# BM1397_TESTBED.net
KiCad netlist of a schematic drawn in Altium Designer
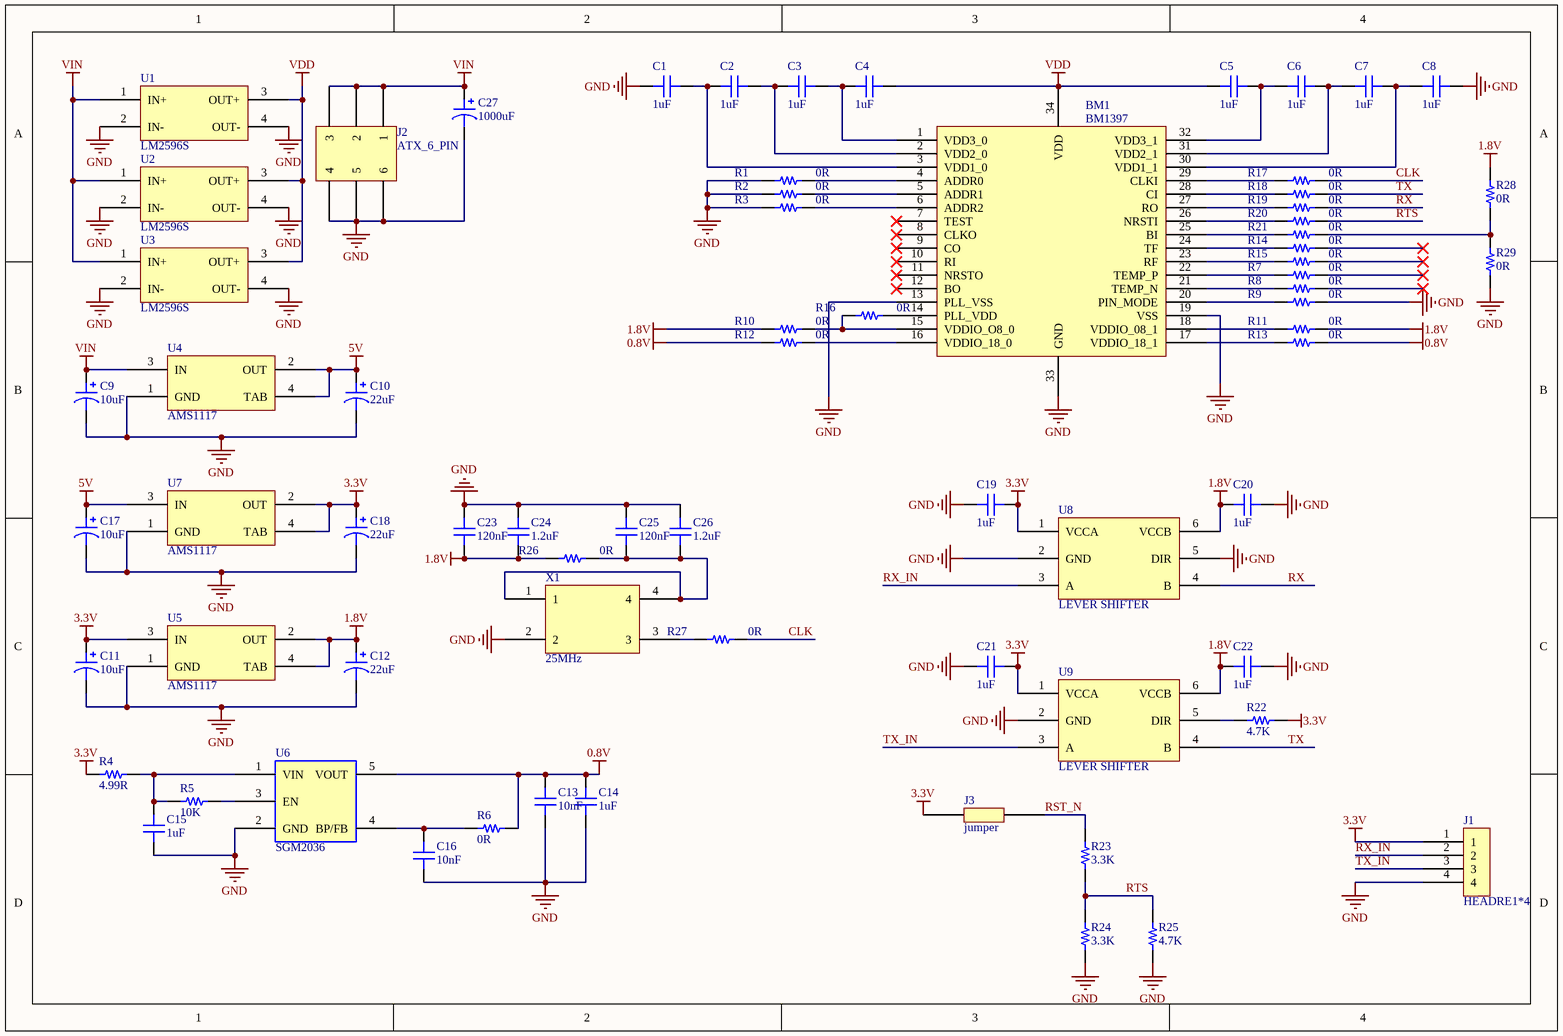
[diagram p0: BM1397_TESTBED.SchDoc]

(export (version "E")
  (design (tool "Eeschema 10.0.6"))
  (components
    (comp (ref "BM1")
      (value "BM1397")
      (footprint "Connector")
      (libsource (lib "BM1397_TESTBED") (part "BM1397_0"))
    )
    (comp (ref "C1") (value "1uF") (footprint "CAP_SMD_0805") (libsource (lib "BM1397_TESTBED") (part "CAP")))
    (comp (ref "C2") (value "1uF") (footprint "CAP_SMD_0805") (libsource (lib "BM1397_TESTBED") (part "CAP")))
    (comp (ref "C3") (value "1uF") (footprint "CAP_SMD_0805") (libsource (lib "BM1397_TESTBED") (part "CAP")))
    (comp (ref "C4") (value "1uF") (footprint "CAP_SMD_0805") (libsource (lib "BM1397_TESTBED") (part "CAP")))
    (comp (ref "C5") (value "1uF") (footprint "CAP_SMD_0805") (libsource (lib "BM1397_TESTBED") (part "CAP")))
    (comp (ref "C6") (value "1uF") (footprint "CAP_SMD_0805") (libsource (lib "BM1397_TESTBED") (part "CAP")))
    (comp (ref "C7") (value "1uF") (footprint "CAP_SMD_0805") (libsource (lib "BM1397_TESTBED") (part "CAP")))
    (comp (ref "C8") (value "1uF") (footprint "CAP_SMD_0805") (libsource (lib "BM1397_TESTBED") (part "CAP")))
    (comp (ref "C9")
      (value "10uF")
      (footprint "CAP-TAN-CASE-B")
      (libsource (lib "BM1397_TESTBED") (part "POLARIZED CAP"))
    )
    (comp (ref "C10")
      (value "22uF")
      (footprint "CAP-TAN-CASE-B")
      (libsource (lib "BM1397_TESTBED") (part "POLARIZED CAP"))
    )
    (comp (ref "C11")
      (value "10uF")
      (footprint "CAP-TAN-CASE-B")
      (libsource (lib "BM1397_TESTBED") (part "POLARIZED CAP"))
    )
    (comp (ref "C12")
      (value "22uF")
      (footprint "CAP-TAN-CASE-B")
      (libsource (lib "BM1397_TESTBED") (part "POLARIZED CAP"))
    )
    (comp (ref "C13")
      (value "10nF")
      (footprint "CAP_SMD_0805")
      (libsource (lib "BM1397_TESTBED") (part "CAP"))
    )
    (comp (ref "C14")
      (value "1uF")
      (footprint "CAP_SMD_0805")
      (libsource (lib "BM1397_TESTBED") (part "CAP"))
    )
    (comp (ref "C15")
      (value "1uF")
      (footprint "CAP_SMD_0805")
      (libsource (lib "BM1397_TESTBED") (part "CAP"))
    )
    (comp (ref "C16")
      (value "10nF")
      (footprint "CAP_SMD_0805")
      (libsource (lib "BM1397_TESTBED") (part "CAP"))
    )
    (comp (ref "C17")
      (value "10uF")
      (footprint "CAP-TAN-CASE-B")
      (libsource (lib "BM1397_TESTBED") (part "POLARIZED CAP"))
    )
    (comp (ref "C18")
      (value "22uF")
      (footprint "CAP-TAN-CASE-B")
      (libsource (lib "BM1397_TESTBED") (part "POLARIZED CAP"))
    )
    (comp (ref "C19")
      (value "1uF")
      (footprint "CAP_SMD_0805")
      (libsource (lib "BM1397_TESTBED") (part "CAP"))
    )
    (comp (ref "C20")
      (value "1uF")
      (footprint "CAP_SMD_0805")
      (libsource (lib "BM1397_TESTBED") (part "CAP"))
    )
    (comp (ref "C21")
      (value "1uF")
      (footprint "CAP_SMD_0805")
      (libsource (lib "BM1397_TESTBED") (part "CAP"))
    )
    (comp (ref "C22")
      (value "1uF")
      (footprint "CAP_SMD_0805")
      (libsource (lib "BM1397_TESTBED") (part "CAP"))
    )
    (comp (ref "C23")
      (value "120nF")
      (footprint "CAP_SMD_1206")
      (libsource (lib "BM1397_TESTBED") (part "CAP"))
    )
    (comp (ref "C24")
      (value "1.2uF")
      (footprint "CAP_SMD_1206")
      (libsource (lib "BM1397_TESTBED") (part "CAP"))
    )
    (comp (ref "C25")
      (value "120nF")
      (footprint "CAP_SMD_1206")
      (libsource (lib "BM1397_TESTBED") (part "CAP"))
    )
    (comp (ref "C26")
      (value "1.2uF")
      (footprint "CAP_SMD_1206")
      (libsource (lib "BM1397_TESTBED") (part "CAP"))
    )
    (comp (ref "C27")
      (value "1000uF")
      (footprint "CAP_POL")
      (libsource (lib "BM1397_TESTBED") (part "POLARIZED CAP"))
    )
    (comp (ref "J1")
      (value "HEADRE1*4")
      (footprint "HEADER-1x4")
      (libsource (lib "BM1397_TESTBED") (part "HEADER-1x4"))
    )
    (comp (ref "J2")
      (value "ATX_6_PIN")
      (footprint "ATX 6")
      (description "ATX PWR CONN 6 PIN")
      (libsource (lib "BM1397_TESTBED") (part "ATX_6_PIN"))
    )
    (comp (ref "J3")
      (value "jumper")
      (footprint "jumper_2pin")
      (libsource (lib "BM1397_TESTBED") (part "Jumper_2"))
    )
    (comp (ref "R1") (value "0R") (footprint "RES-SMD-1206") (libsource (lib "BM1397_TESTBED") (part "RES")))
    (comp (ref "R2") (value "0R") (footprint "RES-SMD-1206") (libsource (lib "BM1397_TESTBED") (part "RES")))
    (comp (ref "R3") (value "0R") (footprint "RES-SMD-1206") (libsource (lib "BM1397_TESTBED") (part "RES")))
    (comp (ref "R4")
      (value "4.99R")
      (footprint "RES-SMD-1206")
      (libsource (lib "BM1397_TESTBED") (part "RES"))
    )
    (comp (ref "R5") (value "10K") (footprint "RES-SMD-1206") (libsource (lib "BM1397_TESTBED") (part "RES")))
    (comp (ref "R6") (value "0R") (footprint "RES-SMD-1206") (libsource (lib "BM1397_TESTBED") (part "RES")))
    (comp (ref "R7") (value "0R") (footprint "RES-SMD-1206") (libsource (lib "BM1397_TESTBED") (part "RES")))
    (comp (ref "R8") (value "0R") (footprint "RES-SMD-1206") (libsource (lib "BM1397_TESTBED") (part "RES")))
    (comp (ref "R9") (value "0R") (footprint "RES-SMD-1206") (libsource (lib "BM1397_TESTBED") (part "RES")))
    (comp (ref "R10") (value "0R") (footprint "RES-SMD-1206") (libsource (lib "BM1397_TESTBED") (part "RES")))
    (comp (ref "R11") (value "0R") (footprint "RES-SMD-1206") (libsource (lib "BM1397_TESTBED") (part "RES")))
    (comp (ref "R12") (value "0R") (footprint "RES-SMD-1206") (libsource (lib "BM1397_TESTBED") (part "RES")))
    (comp (ref "R13") (value "0R") (footprint "RES-SMD-1206") (libsource (lib "BM1397_TESTBED") (part "RES")))
    (comp (ref "R14") (value "0R") (footprint "RES-SMD-1206") (libsource (lib "BM1397_TESTBED") (part "RES")))
    (comp (ref "R15") (value "0R") (footprint "RES-SMD-1206") (libsource (lib "BM1397_TESTBED") (part "RES")))
    (comp (ref "R16") (value "0R") (footprint "RES-SMD-1206") (libsource (lib "BM1397_TESTBED") (part "RES")))
    (comp (ref "R17") (value "0R") (footprint "RES-SMD-1206") (libsource (lib "BM1397_TESTBED") (part "RES")))
    (comp (ref "R18") (value "0R") (footprint "RES-SMD-1206") (libsource (lib "BM1397_TESTBED") (part "RES")))
    (comp (ref "R19") (value "0R") (footprint "RES-SMD-1206") (libsource (lib "BM1397_TESTBED") (part "RES")))
    (comp (ref "R20") (value "0R") (footprint "RES-SMD-1206") (libsource (lib "BM1397_TESTBED") (part "RES")))
    (comp (ref "R21") (value "0R") (footprint "RES-SMD-1206") (libsource (lib "BM1397_TESTBED") (part "RES")))
    (comp (ref "R22")
      (value "4.7K")
      (footprint "RES-SMD-1206")
      (libsource (lib "BM1397_TESTBED") (part "RES"))
    )
    (comp (ref "R23")
      (value "3.3K")
      (footprint "RES-SMD-1206")
      (libsource (lib "BM1397_TESTBED") (part "RES"))
    )
    (comp (ref "R24")
      (value "3.3K")
      (footprint "RES-SMD-1206")
      (libsource (lib "BM1397_TESTBED") (part "RES"))
    )
    (comp (ref "R25")
      (value "4.7K")
      (footprint "RES-SMD-1206")
      (libsource (lib "BM1397_TESTBED") (part "RES"))
    )
    (comp (ref "R26") (value "0R") (footprint "RES-SMD-1206") (libsource (lib "BM1397_TESTBED") (part "RES")))
    (comp (ref "R27") (value "0R") (footprint "RES-SMD-1206") (libsource (lib "BM1397_TESTBED") (part "RES")))
    (comp (ref "R28") (value "0R") (footprint "RES-SMD-1206") (libsource (lib "BM1397_TESTBED") (part "RES")))
    (comp (ref "R29") (value "0R") (footprint "RES-SMD-1206") (libsource (lib "BM1397_TESTBED") (part "RES")))
    (comp (ref "U1")
      (value "LM2596S")
      (footprint "LM2596S")
      (description "DC-DC CONVERTER")
      (libsource (lib "BM1397_TESTBED") (part "LM2596s"))
    )
    (comp (ref "U2")
      (value "LM2596S")
      (footprint "LM2596S")
      (description "DC-DC CONVERTER")
      (libsource (lib "BM1397_TESTBED") (part "LM2596s"))
    )
    (comp (ref "U3")
      (value "LM2596S")
      (footprint "LM2596S")
      (description "DC-DC CONVERTER")
      (libsource (lib "BM1397_TESTBED") (part "LM2596s"))
    )
    (comp (ref "U4")
      (value "AMS1117")
      (footprint "AMS1117")
      (libsource (lib "BM1397_TESTBED") (part "AMS1117"))
    )
    (comp (ref "U5")
      (value "AMS1117")
      (footprint "AMS1117")
      (libsource (lib "BM1397_TESTBED") (part "AMS1117"))
    )
    (comp (ref "U6")
      (value "SGM2036")
      (footprint "SOT23-5PIN")
      (libsource (lib "BM1397_TESTBED") (part "SGM2036"))
    )
    (comp (ref "U7")
      (value "AMS1117")
      (footprint "AMS1117")
      (libsource (lib "BM1397_TESTBED") (part "AMS1117"))
    )
    (comp (ref "U8")
      (value "LEVER SHIFTER")
      (footprint "SOT23-6PIN")
      (libsource (lib "BM1397_TESTBED") (part "SN74LVC1T45"))
    )
    (comp (ref "U9")
      (value "LEVER SHIFTER")
      (footprint "SOT23-6PIN")
      (libsource (lib "BM1397_TESTBED") (part "SN74LVC1T45"))
    )
    (comp (ref "X1") (value "25MHz") (footprint "XTALL") (libsource (lib "BM1397_TESTBED") (part "XTALL")))
  )
  (nets
    (net (code "1") (name "/CLK") (class "Default")
      (node (ref "R17") (pin "2") (pinfunction "2_2") (pintype "passive"))
      (node (ref "R27") (pin "2") (pinfunction "2_2") (pintype "passive"))
    )
    (net (code "2") (name "/RST_N") (class "Default")
      (node (ref "J3") (pin "2") (pinfunction "2_2") (pintype "passive"))
      (node (ref "R23") (pin "2") (pinfunction "2_2") (pintype "passive"))
    )
    (net (code "3") (name "/RTS") (class "Default")
      (node (ref "R20") (pin "2") (pinfunction "2_2") (pintype "passive"))
      (node (ref "R23") (pin "1") (pinfunction "1_1") (pintype "passive"))
      (node (ref "R24") (pin "2") (pinfunction "2_2") (pintype "passive"))
      (node (ref "R25") (pin "2") (pinfunction "2_2") (pintype "passive"))
    )
    (net (code "4") (name "/RX") (class "Default")
      (node (ref "R19") (pin "2") (pinfunction "2_2") (pintype "passive"))
      (node (ref "U8") (pin "4") (pinfunction "B_4") (pintype "passive"))
    )
    (net (code "5") (name "/RX_IN") (class "Default")
      (node (ref "J1") (pin "2") (pinfunction "2_2") (pintype "passive"))
      (node (ref "U8") (pin "3") (pinfunction "A_3") (pintype "passive"))
    )
    (net (code "6") (name "/TX") (class "Default")
      (node (ref "R18") (pin "2") (pinfunction "2_2") (pintype "passive"))
      (node (ref "U9") (pin "4") (pinfunction "B_4") (pintype "passive"))
    )
    (net (code "7") (name "/TX_IN") (class "Default")
      (node (ref "J1") (pin "3") (pinfunction "3_3") (pintype "passive"))
      (node (ref "U9") (pin "3") (pinfunction "A_3") (pintype "passive"))
    )
    (net (code "8") (name "0.8V") (class "Default")
      (node (ref "C13") (pin "2") (pinfunction "2_2") (pintype "passive"))
      (node (ref "C14") (pin "2") (pinfunction "2_2") (pintype "passive"))
      (node (ref "R12") (pin "1") (pinfunction "1_1") (pintype "passive"))
      (node (ref "R13") (pin "2") (pinfunction "2_2") (pintype "passive"))
      (node (ref "R6") (pin "2") (pinfunction "2_2") (pintype "passive"))
      (node (ref "U6") (pin "5") (pinfunction "VOUT_5") (pintype "passive"))
    )
    (net (code "9") (name "1.8V") (class "Default")
      (node (ref "C12") (pin "1") (pinfunction "1_1") (pintype "passive"))
      (node (ref "C20") (pin "1") (pinfunction "1_1") (pintype "passive"))
      (node (ref "C22") (pin "1") (pinfunction "1_1") (pintype "passive"))
      (node (ref "C23") (pin "1") (pinfunction "1_1") (pintype "passive"))
      (node (ref "C24") (pin "1") (pinfunction "1_1") (pintype "passive"))
      (node (ref "R10") (pin "1") (pinfunction "1_1") (pintype "passive"))
      (node (ref "R11") (pin "2") (pinfunction "2_2") (pintype "passive"))
      (node (ref "R26") (pin "1") (pinfunction "1_1") (pintype "passive"))
      (node (ref "R28") (pin "2") (pinfunction "2_2") (pintype "passive"))
      (node (ref "U5") (pin "2") (pinfunction "OUT_2") (pintype "passive"))
      (node (ref "U5") (pin "4") (pinfunction "TAB_4") (pintype "passive"))
      (node (ref "U8") (pin "6") (pinfunction "VCCB_6") (pintype "passive"))
      (node (ref "U9") (pin "6") (pinfunction "VCCB_6") (pintype "passive"))
    )
    (net (code "10") (name "3.3V") (class "Default")
      (node (ref "C11") (pin "1") (pinfunction "1_1") (pintype "passive"))
      (node (ref "C18") (pin "1") (pinfunction "1_1") (pintype "passive"))
      (node (ref "C19") (pin "2") (pinfunction "2_2") (pintype "passive"))
      (node (ref "C21") (pin "2") (pinfunction "2_2") (pintype "passive"))
      (node (ref "J1") (pin "1") (pinfunction "1_1") (pintype "passive"))
      (node (ref "J3") (pin "1") (pinfunction "1_1") (pintype "passive"))
      (node (ref "R22") (pin "2") (pinfunction "2_2") (pintype "passive"))
      (node (ref "R4") (pin "1") (pinfunction "1_1") (pintype "passive"))
      (node (ref "U5") (pin "3") (pinfunction "IN_3") (pintype "passive"))
      (node (ref "U7") (pin "2") (pinfunction "OUT_2") (pintype "passive"))
      (node (ref "U7") (pin "4") (pinfunction "TAB_4") (pintype "passive"))
      (node (ref "U8") (pin "1") (pinfunction "VCCA_1") (pintype "passive"))
      (node (ref "U9") (pin "1") (pinfunction "VCCA_1") (pintype "passive"))
    )
    (net (code "11") (name "5V") (class "Default")
      (node (ref "C10") (pin "1") (pinfunction "1_1") (pintype "passive"))
      (node (ref "C17") (pin "1") (pinfunction "1_1") (pintype "passive"))
      (node (ref "U4") (pin "2") (pinfunction "OUT_2") (pintype "passive"))
      (node (ref "U4") (pin "4") (pinfunction "TAB_4") (pintype "passive"))
      (node (ref "U7") (pin "3") (pinfunction "IN_3") (pintype "passive"))
    )
    (net (code "12") (name "GND") (class "Default")
      (node (ref "BM1") (pin "13") (pinfunction "PLL_VSS_13") (pintype "passive"))
      (node (ref "BM1") (pin "19") (pinfunction "VSS_19") (pintype "passive"))
      (node (ref "BM1") (pin "33") (pinfunction "GND_33") (pintype "passive"))
      (node (ref "C1") (pin "1") (pinfunction "1_1") (pintype "passive"))
      (node (ref "C10") (pin "2") (pinfunction "2_2") (pintype "passive"))
      (node (ref "C11") (pin "2") (pinfunction "2_2") (pintype "passive"))
      (node (ref "C12") (pin "2") (pinfunction "2_2") (pintype "passive"))
      (node (ref "C13") (pin "1") (pinfunction "1_1") (pintype "passive"))
      (node (ref "C14") (pin "1") (pinfunction "1_1") (pintype "passive"))
      (node (ref "C15") (pin "1") (pinfunction "1_1") (pintype "passive"))
      (node (ref "C16") (pin "1") (pinfunction "1_1") (pintype "passive"))
      (node (ref "C17") (pin "2") (pinfunction "2_2") (pintype "passive"))
      (node (ref "C18") (pin "2") (pinfunction "2_2") (pintype "passive"))
      (node (ref "C19") (pin "1") (pinfunction "1_1") (pintype "passive"))
      (node (ref "C20") (pin "2") (pinfunction "2_2") (pintype "passive"))
      (node (ref "C21") (pin "1") (pinfunction "1_1") (pintype "passive"))
      (node (ref "C22") (pin "2") (pinfunction "2_2") (pintype "passive"))
      (node (ref "C23") (pin "2") (pinfunction "2_2") (pintype "passive"))
      (node (ref "C24") (pin "2") (pinfunction "2_2") (pintype "passive"))
      (node (ref "C25") (pin "2") (pinfunction "2_2") (pintype "passive"))
      (node (ref "C26") (pin "2") (pinfunction "2_2") (pintype "passive"))
      (node (ref "C27") (pin "2") (pinfunction "2_2") (pintype "passive"))
      (node (ref "C8") (pin "2") (pinfunction "2_2") (pintype "passive"))
      (node (ref "C9") (pin "2") (pinfunction "2_2") (pintype "passive"))
      (node (ref "J1") (pin "4") (pinfunction "4_4") (pintype "passive"))
      (node (ref "J2") (pin "4") (pinfunction "4_4") (pintype "passive"))
      (node (ref "J2") (pin "5") (pinfunction "5_5") (pintype "passive"))
      (node (ref "J2") (pin "6") (pinfunction "6_6") (pintype "passive"))
      (node (ref "R1") (pin "1") (pinfunction "1_1") (pintype "passive"))
      (node (ref "R2") (pin "1") (pinfunction "1_1") (pintype "passive"))
      (node (ref "R24") (pin "1") (pinfunction "1_1") (pintype "passive"))
      (node (ref "R25") (pin "1") (pinfunction "1_1") (pintype "passive"))
      (node (ref "R29") (pin "1") (pinfunction "1_1") (pintype "passive"))
      (node (ref "R3") (pin "1") (pinfunction "1_1") (pintype "passive"))
      (node (ref "R9") (pin "2") (pinfunction "2_2") (pintype "passive"))
      (node (ref "U1") (pin "2") (pinfunction "IN-_2") (pintype "passive"))
      (node (ref "U1") (pin "4") (pinfunction "OUT-_4") (pintype "passive"))
      (node (ref "U2") (pin "2") (pinfunction "IN-_2") (pintype "passive"))
      (node (ref "U2") (pin "4") (pinfunction "OUT-_4") (pintype "passive"))
      (node (ref "U3") (pin "2") (pinfunction "IN-_2") (pintype "passive"))
      (node (ref "U3") (pin "4") (pinfunction "OUT-_4") (pintype "passive"))
      (node (ref "U4") (pin "1") (pinfunction "GND_1") (pintype "passive"))
      (node (ref "U5") (pin "1") (pinfunction "GND_1") (pintype "passive"))
      (node (ref "U6") (pin "2") (pinfunction "GND_2") (pintype "passive"))
      (node (ref "U7") (pin "1") (pinfunction "GND_1") (pintype "passive"))
      (node (ref "U8") (pin "2") (pinfunction "GND_2") (pintype "passive"))
      (node (ref "U8") (pin "5") (pinfunction "DIR_5") (pintype "passive"))
      (node (ref "U9") (pin "2") (pinfunction "GND_2") (pintype "passive"))
      (node (ref "X1") (pin "2") (pinfunction "2_2") (pintype "passive"))
    )
    (net (code "13") (name "Net-(BM1-ADDR0)") (class "Default")
      (node (ref "BM1") (pin "4") (pinfunction "ADDR0_4") (pintype "passive"))
      (node (ref "R1") (pin "2") (pinfunction "2_2") (pintype "passive"))
    )
    (net (code "14") (name "Net-(BM1-ADDR1)") (class "Default")
      (node (ref "BM1") (pin "5") (pinfunction "ADDR1_5") (pintype "passive"))
      (node (ref "R2") (pin "2") (pinfunction "2_2") (pintype "passive"))
    )
    (net (code "15") (name "Net-(BM1-ADDR2)") (class "Default")
      (node (ref "BM1") (pin "6") (pinfunction "ADDR2_6") (pintype "passive"))
      (node (ref "R3") (pin "2") (pinfunction "2_2") (pintype "passive"))
    )
    (net (code "16") (name "Net-(BM1-BI)") (class "Default")
      (node (ref "BM1") (pin "25") (pinfunction "BI_25") (pintype "passive"))
      (node (ref "R21") (pin "1") (pinfunction "1_1") (pintype "passive"))
    )
    (net (code "17") (name "Net-(BM1-CI)") (class "Default")
      (node (ref "BM1") (pin "28") (pinfunction "CI_28") (pintype "passive"))
      (node (ref "R18") (pin "1") (pinfunction "1_1") (pintype "passive"))
    )
    (net (code "18") (name "Net-(BM1-CLKI)") (class "Default")
      (node (ref "BM1") (pin "29") (pinfunction "CLKI_29") (pintype "passive"))
      (node (ref "R17") (pin "1") (pinfunction "1_1") (pintype "passive"))
    )
    (net (code "19") (name "Net-(BM1-NRSTI)") (class "Default")
      (node (ref "BM1") (pin "26") (pinfunction "NRSTI_26") (pintype "passive"))
      (node (ref "R20") (pin "1") (pinfunction "1_1") (pintype "passive"))
    )
    (net (code "20") (name "Net-(BM1-PIN_MODE)") (class "Default")
      (node (ref "BM1") (pin "20") (pinfunction "PIN_MODE_20") (pintype "passive"))
      (node (ref "R9") (pin "1") (pinfunction "1_1") (pintype "passive"))
    )
    (net (code "21") (name "Net-(BM1-PLL_VDD)") (class "Default")
      (node (ref "BM1") (pin "14") (pinfunction "PLL_VDD_14") (pintype "passive"))
      (node (ref "R16") (pin "2") (pinfunction "2_2") (pintype "passive"))
    )
    (net (code "22") (name "Net-(BM1-RF)") (class "Default")
      (node (ref "BM1") (pin "23") (pinfunction "RF_23") (pintype "passive"))
      (node (ref "R15") (pin "1") (pinfunction "1_1") (pintype "passive"))
    )
    (net (code "23") (name "Net-(BM1-RO)") (class "Default")
      (node (ref "BM1") (pin "27") (pinfunction "RO_27") (pintype "passive"))
      (node (ref "R19") (pin "1") (pinfunction "1_1") (pintype "passive"))
    )
    (net (code "24") (name "Net-(BM1-TEMP_N)") (class "Default")
      (node (ref "BM1") (pin "21") (pinfunction "TEMP_N_21") (pintype "passive"))
      (node (ref "R8") (pin "1") (pinfunction "1_1") (pintype "passive"))
    )
    (net (code "25") (name "Net-(BM1-TEMP_P)") (class "Default")
      (node (ref "BM1") (pin "22") (pinfunction "TEMP_P_22") (pintype "passive"))
      (node (ref "R7") (pin "1") (pinfunction "1_1") (pintype "passive"))
    )
    (net (code "26") (name "Net-(BM1-TF)") (class "Default")
      (node (ref "BM1") (pin "24") (pinfunction "TF_24") (pintype "passive"))
      (node (ref "R14") (pin "1") (pinfunction "1_1") (pintype "passive"))
    )
    (net (code "27") (name "Net-(BM1-VDD1_0)") (class "Default")
      (node (ref "BM1") (pin "3") (pinfunction "VDD1_0_3") (pintype "passive"))
      (node (ref "C1") (pin "2") (pinfunction "2_2") (pintype "passive"))
      (node (ref "C2") (pin "1") (pinfunction "1_1") (pintype "passive"))
    )
    (net (code "28") (name "Net-(BM1-VDD1_1)") (class "Default")
      (node (ref "BM1") (pin "30") (pinfunction "VDD1_1_30") (pintype "passive"))
      (node (ref "C7") (pin "2") (pinfunction "2_2") (pintype "passive"))
      (node (ref "C8") (pin "1") (pinfunction "1_1") (pintype "passive"))
    )
    (net (code "29") (name "Net-(BM1-VDD2_0)") (class "Default")
      (node (ref "BM1") (pin "2") (pinfunction "VDD2_0_2") (pintype "passive"))
      (node (ref "C2") (pin "2") (pinfunction "2_2") (pintype "passive"))
      (node (ref "C3") (pin "1") (pinfunction "1_1") (pintype "passive"))
    )
    (net (code "30") (name "Net-(BM1-VDD2_1)") (class "Default")
      (node (ref "BM1") (pin "31") (pinfunction "VDD2_1_31") (pintype "passive"))
      (node (ref "C6") (pin "2") (pinfunction "2_2") (pintype "passive"))
      (node (ref "C7") (pin "1") (pinfunction "1_1") (pintype "passive"))
    )
    (net (code "31") (name "Net-(BM1-VDD3_0)") (class "Default")
      (node (ref "BM1") (pin "1") (pinfunction "VDD3_0_1") (pintype "passive"))
      (node (ref "C3") (pin "2") (pinfunction "2_2") (pintype "passive"))
      (node (ref "C4") (pin "1") (pinfunction "1_1") (pintype "passive"))
    )
    (net (code "32") (name "Net-(BM1-VDD3_1)") (class "Default")
      (node (ref "BM1") (pin "32") (pinfunction "VDD3_1_32") (pintype "passive"))
      (node (ref "C5") (pin "2") (pinfunction "2_2") (pintype "passive"))
      (node (ref "C6") (pin "1") (pinfunction "1_1") (pintype "passive"))
    )
    (net (code "33") (name "Net-(BM1-VDDIO_08_1)") (class "Default")
      (node (ref "BM1") (pin "18") (pinfunction "VDDIO_08_1_18") (pintype "passive"))
      (node (ref "R11") (pin "1") (pinfunction "1_1") (pintype "passive"))
    )
    (net (code "34") (name "Net-(BM1-VDDIO_18_0)") (class "Default")
      (node (ref "BM1") (pin "16") (pinfunction "VDDIO_18_0_16") (pintype "passive"))
      (node (ref "R12") (pin "2") (pinfunction "2_2") (pintype "passive"))
    )
    (net (code "35") (name "Net-(BM1-VDDIO_18_1)") (class "Default")
      (node (ref "BM1") (pin "17") (pinfunction "VDDIO_18_1_17") (pintype "passive"))
      (node (ref "R13") (pin "1") (pinfunction "1_1") (pintype "passive"))
    )
    (net (code "36") (name "Net-(BM1-VDDIO_O8_0)") (class "Default")
      (node (ref "BM1") (pin "15") (pinfunction "VDDIO_O8_0_15") (pintype "passive"))
      (node (ref "R10") (pin "2") (pinfunction "2_2") (pintype "passive"))
      (node (ref "R16") (pin "1") (pinfunction "1_1") (pintype "passive"))
    )
    (net (code "37") (name "Net-(C25-Pad1)") (class "Default")
      (node (ref "C25") (pin "1") (pinfunction "1_1") (pintype "passive"))
      (node (ref "C26") (pin "1") (pinfunction "1_1") (pintype "passive"))
      (node (ref "R26") (pin "2") (pinfunction "2_2") (pintype "passive"))
      (node (ref "X1") (pin "1") (pinfunction "1_1") (pintype "passive"))
      (node (ref "X1") (pin "4") (pinfunction "4_4") (pintype "passive"))
    )
    (net (code "38") (name "Net-(R21-Pad2)") (class "Default")
      (node (ref "R21") (pin "2") (pinfunction "2_2") (pintype "passive"))
      (node (ref "R28") (pin "1") (pinfunction "1_1") (pintype "passive"))
      (node (ref "R29") (pin "2") (pinfunction "2_2") (pintype "passive"))
    )
    (net (code "39") (name "Net-(R27-Pad1)") (class "Default")
      (node (ref "R27") (pin "1") (pinfunction "1_1") (pintype "passive"))
      (node (ref "X1") (pin "3") (pinfunction "3_3") (pintype "passive"))
    )
    (net (code "40") (name "Net-(U6-BP{slash}FB)") (class "Default")
      (node (ref "C16") (pin "2") (pinfunction "2_2") (pintype "passive"))
      (node (ref "R6") (pin "1") (pinfunction "1_1") (pintype "passive"))
      (node (ref "U6") (pin "4") (pinfunction "BP/FB_4") (pintype "passive"))
    )
    (net (code "41") (name "Net-(U6-EN)") (class "Default")
      (node (ref "R5") (pin "2") (pinfunction "2_2") (pintype "passive"))
      (node (ref "U6") (pin "3") (pinfunction "EN_3") (pintype "passive"))
    )
    (net (code "42") (name "Net-(U6-VIN)") (class "Default")
      (node (ref "C15") (pin "2") (pinfunction "2_2") (pintype "passive"))
      (node (ref "R4") (pin "2") (pinfunction "2_2") (pintype "passive"))
      (node (ref "R5") (pin "1") (pinfunction "1_1") (pintype "passive"))
      (node (ref "U6") (pin "1") (pinfunction "VIN_1") (pintype "passive"))
    )
    (net (code "43") (name "Net-(U9-DIR)") (class "Default")
      (node (ref "R22") (pin "1") (pinfunction "1_1") (pintype "passive"))
      (node (ref "U9") (pin "5") (pinfunction "DIR_5") (pintype "passive"))
    )
    (net (code "44") (name "VDD") (class "Default")
      (node (ref "BM1") (pin "34") (pinfunction "VDD_34") (pintype "passive"))
      (node (ref "C4") (pin "2") (pinfunction "2_2") (pintype "passive"))
      (node (ref "C5") (pin "1") (pinfunction "1_1") (pintype "passive"))
      (node (ref "U1") (pin "3") (pinfunction "OUT+_3") (pintype "passive"))
      (node (ref "U2") (pin "3") (pinfunction "OUT+_3") (pintype "passive"))
      (node (ref "U3") (pin "3") (pinfunction "OUT+_3") (pintype "passive"))
    )
    (net (code "45") (name "VIN") (class "Default")
      (node (ref "C27") (pin "1") (pinfunction "1_1") (pintype "passive"))
      (node (ref "C9") (pin "1") (pinfunction "1_1") (pintype "passive"))
      (node (ref "J2") (pin "1") (pinfunction "1_1") (pintype "passive"))
      (node (ref "J2") (pin "2") (pinfunction "2_2") (pintype "passive"))
      (node (ref "J2") (pin "3") (pinfunction "3_3") (pintype "passive"))
      (node (ref "U1") (pin "1") (pinfunction "IN+_1") (pintype "passive"))
      (node (ref "U2") (pin "1") (pinfunction "IN+_1") (pintype "passive"))
      (node (ref "U3") (pin "1") (pinfunction "IN+_1") (pintype "passive"))
      (node (ref "U4") (pin "3") (pinfunction "IN_3") (pintype "passive"))
    )
    (net (code "46") (name "unconnected-(BM1-BO-Pad12)") (class "Default")
      (node (ref "BM1") (pin "12") (pinfunction "BO_12") (pintype "passive+no_connect"))
    )
    (net (code "47") (name "unconnected-(BM1-CLKO-Pad8)") (class "Default")
      (node (ref "BM1") (pin "8") (pinfunction "CLKO_8") (pintype "passive+no_connect"))
    )
    (net (code "48") (name "unconnected-(BM1-CO-Pad9)") (class "Default")
      (node (ref "BM1") (pin "9") (pinfunction "CO_9") (pintype "passive+no_connect"))
    )
    (net (code "49") (name "unconnected-(BM1-NRSTO-Pad11)") (class "Default")
      (node (ref "BM1") (pin "11") (pinfunction "NRSTO_11") (pintype "passive+no_connect"))
    )
    (net (code "50") (name "unconnected-(BM1-RI-Pad10)") (class "Default")
      (node (ref "BM1") (pin "10") (pinfunction "RI_10") (pintype "passive+no_connect"))
    )
    (net (code "51") (name "unconnected-(BM1-TEST-Pad7)") (class "Default")
      (node (ref "BM1") (pin "7") (pinfunction "TEST_7") (pintype "passive+no_connect"))
    )
    (net (code "52") (name "unconnected-(R7-Pad2)") (class "Default")
      (node (ref "R7") (pin "2") (pinfunction "2_2") (pintype "passive+no_connect"))
    )
    (net (code "53") (name "unconnected-(R8-Pad2)") (class "Default")
      (node (ref "R8") (pin "2") (pinfunction "2_2") (pintype "passive+no_connect"))
    )
    (net (code "54") (name "unconnected-(R14-Pad2)") (class "Default")
      (node (ref "R14") (pin "2") (pinfunction "2_2") (pintype "passive+no_connect"))
    )
    (net (code "55") (name "unconnected-(R15-Pad2)") (class "Default")
      (node (ref "R15") (pin "2") (pinfunction "2_2") (pintype "passive+no_connect"))
    )
  )
)
